# MB85RC1MT.net
KiCad netlist of a schematic drawn in EAGLE
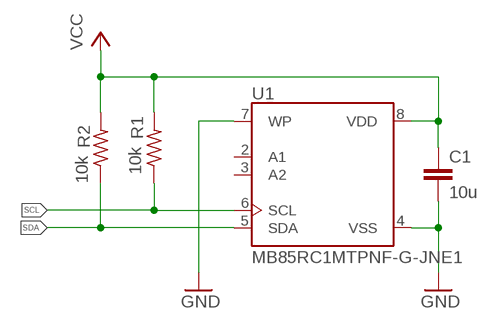
[diagram p0: schematic, sheet 1]

(export (version "E")
  (design (tool "Eeschema 10.0.6"))
  (components
    (comp (ref "C1")
      (value "10u")
      (footprint "eagle-import:C0603")
      (libsource (lib "eagle-import") (part "C-EUC0603"))
    )
    (comp (ref "R1")
      (value "10k")
      (footprint "eagle-import:R0603")
      (libsource (lib "eagle-import") (part "R-US_R0603"))
    )
    (comp (ref "R2")
      (value "10k")
      (footprint "eagle-import:R0603")
      (libsource (lib "eagle-import") (part "R-US_R0603"))
    )
    (comp (ref "U1")
      (value "MB85RC1MTPNF-G-JNE1")
      (footprint "eagle-import:SOIC127P620X175-8N")
      (fields (field (name "MF") "Fujitsu"))
      (libsource (lib "eagle-import") (part "MB85RC1MTPNF-G-JNE1"))
    )
  )
  (nets
    (net (code "1") (name "GND") (class "Default")
      (node (ref "C1") (pin "2") (pinfunction "2_2") (pintype "passive"))
      (node (ref "U1") (pin "4") (pinfunction "VSS_4") (pintype "power_in"))
      (node (ref "U1") (pin "7") (pinfunction "WP_7") (pintype "input"))
    )
    (net (code "2") (name "SCL") (class "Default")
      (node (ref "R1") (pin "1") (pinfunction "1_1") (pintype "passive"))
      (node (ref "U1") (pin "6") (pinfunction "SCL_6") (pintype "bidirectional"))
    )
    (net (code "3") (name "SDA") (class "Default")
      (node (ref "R2") (pin "1") (pinfunction "1_1") (pintype "passive"))
      (node (ref "U1") (pin "5") (pinfunction "SDA_5") (pintype "bidirectional"))
    )
    (net (code "4") (name "VCC") (class "Default")
      (node (ref "C1") (pin "1") (pinfunction "1_1") (pintype "passive"))
      (node (ref "R1") (pin "2") (pinfunction "2_2") (pintype "passive"))
      (node (ref "R2") (pin "2") (pinfunction "2_2") (pintype "passive"))
      (node (ref "U1") (pin "8") (pinfunction "VDD_8") (pintype "power_in"))
    )
    (net (code "5") (name "unconnected-(U1-A1-Pad2)") (class "Default")
      (node (ref "U1") (pin "2") (pinfunction "A1_2") (pintype "bidirectional"))
    )
    (net (code "6") (name "unconnected-(U1-A2-Pad3)") (class "Default")
      (node (ref "U1") (pin "3") (pinfunction "A2_3") (pintype "bidirectional"))
    )
  )
)
